# rx_1280.net
KiCad netlist of a schematic drawn in EAGLE
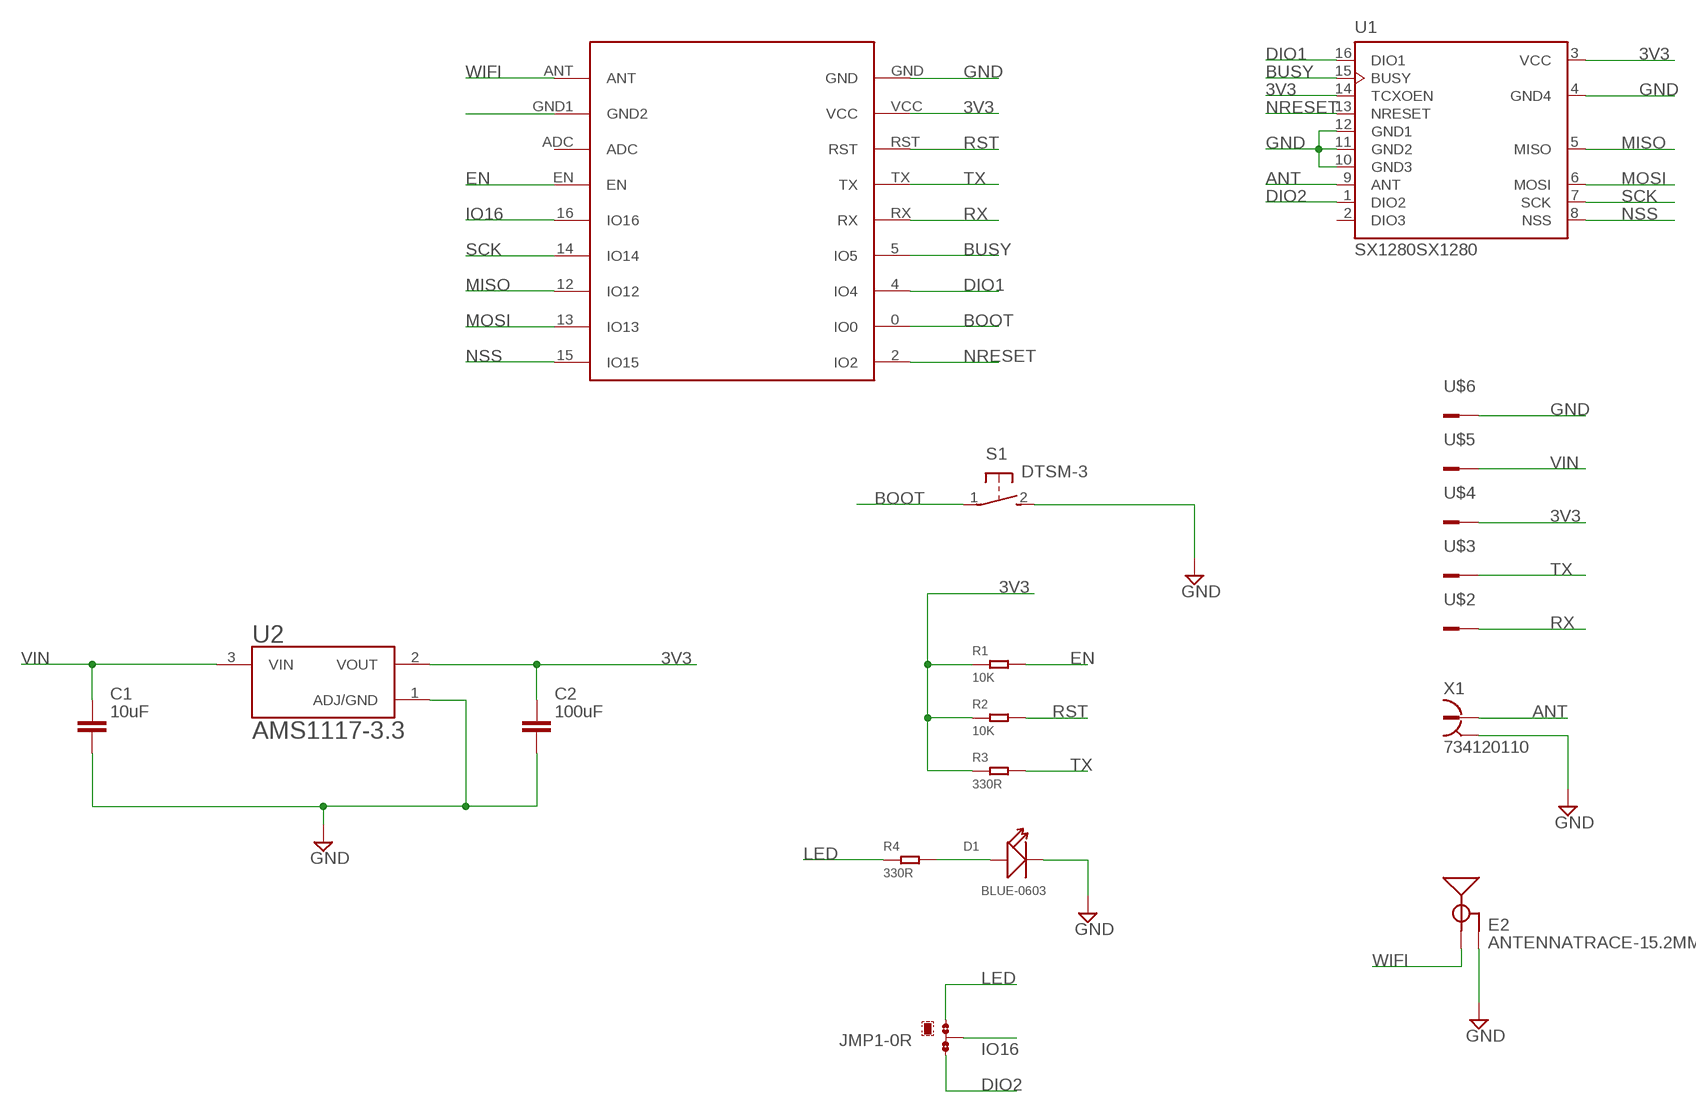
[diagram p0: schematic, sheet 1]

(export (version "E")
  (design (tool "Eeschema 10.0.6"))
  (components
    (comp (ref "C1")
      (value "10uF")
      (footprint "eagle-import:CAPM3528X210")
      (libsource (lib "eagle-import") (part "CTANTALUM-1411(3528-METRIC)_"))
    )
    (comp (ref "C2")
      (value "100uF")
      (footprint "eagle-import:CAPM3528X210")
      (libsource (lib "eagle-import") (part "CTANTALUM-1411(3528-METRIC)_"))
    )
    (comp (ref "D1")
      (value "BLUE-0603")
      (footprint "eagle-import:LED-0603")
      (fields (field (name "MPN") "19-217-BHC-ZL1M2RY-3T"))
      (libsource (lib "eagle-import") (part "SMD-LED-CLEAR-BLUE(0603)"))
    )
    (comp (ref "E2")
      (value "ANTENNATRACE-15.2MM")
      (footprint "eagle-import:TRACE_ANTENNA_2.4GHZ_15.2MM")
      (libsource (lib "eagle-import") (part "ANTENNATRACE-15.2MM"))
    )
    (comp (ref "JMP1")
      (value "0R-JUMPA")
      (footprint "eagle-import:A0R-JMP")
      (libsource (lib "eagle-import") (part "0R-JUMPA"))
    )
    (comp (ref "R1")
      (value "10K")
      (footprint "eagle-import:R0805")
      (fields (field (name "MPN") "RC0805FR-0710KL"))
      (libsource (lib "eagle-import") (part "SMD-RES-10K-1%-1/8W(0805)"))
    )
    (comp (ref "R2")
      (value "10K")
      (footprint "eagle-import:R0805")
      (fields (field (name "MPN") "RC0805FR-0710KL"))
      (libsource (lib "eagle-import") (part "SMD-RES-10K-1%-1/8W(0805)"))
    )
    (comp (ref "R3")
      (value "330R")
      (footprint "eagle-import:R0805")
      (fields (field (name "MPN") "RC0805JR-071KL"))
      (libsource (lib "eagle-import") (part "SMD-RES-330R-5%-1/8W(0805)"))
    )
    (comp (ref "R4")
      (value "330R")
      (footprint "eagle-import:R0805")
      (fields (field (name "MPN") "RC0805JR-071KL"))
      (libsource (lib "eagle-import") (part "SMD-RES-330R-5%-1/8W(0805)"))
    )
    (comp (ref "S1")
      (value "DTSM-3")
      (footprint "eagle-import:DTSM-3")
      (libsource (lib "eagle-import") (part "DTSM-3"))
    )
    (comp (ref "U$1")
      (value "ESP-M2")
      (footprint "eagle-import:ESP-M2")
      (fields
        (field (name "MF") "Doctors of Intelligence & Technology Co., LTD")
        (field (name "MP") " ESP-M2 ")
      )
      (libsource (lib "eagle-import") (part "ESP-M2"))
    )
    (comp (ref "U$2")
      (value "CONN-1")
      (footprint "eagle-import:PAD1")
      (libsource (lib "eagle-import") (part "CONN-1"))
    )
    (comp (ref "U$3")
      (value "CONN-1")
      (footprint "eagle-import:PAD1")
      (libsource (lib "eagle-import") (part "CONN-1"))
    )
    (comp (ref "U$4")
      (value "CONN-1")
      (footprint "eagle-import:PAD1")
      (libsource (lib "eagle-import") (part "CONN-1"))
    )
    (comp (ref "U$5")
      (value "CONN-1")
      (footprint "eagle-import:PAD1")
      (libsource (lib "eagle-import") (part "CONN-1"))
    )
    (comp (ref "U$6")
      (value "CONN-1")
      (footprint "eagle-import:PAD1")
      (libsource (lib "eagle-import") (part "CONN-1"))
    )
    (comp (ref "U1")
      (value "SX1280SX1280")
      (footprint "eagle-import:SX1280")
      (libsource (lib "eagle-import") (part "SX1280SX1280"))
    )
    (comp (ref "U2")
      (value "AMS1117-3.3")
      (footprint "eagle-import:SOT229P700X180-4N")
      (fields (field (name "MF") "Advanced Monolithic Systems"))
      (libsource (lib "eagle-import") (part "AMS1117-3.3"))
    )
    (comp (ref "X1")
      (value "734120110")
      (footprint "eagle-import:734120110")
      (fields (field (name "MF") "Molex") (field (name "MP") "734-12-0110"))
      (libsource (lib "eagle-import") (part "734120110"))
    )
  )
  (nets
    (net (code "1") (name "/3V3") (class "Default")
      (node (ref "C2") (pin "1") (pinfunction "1_1") (pintype "passive"))
      (node (ref "R1") (pin "1") (pinfunction "1_1") (pintype "passive"))
      (node (ref "R2") (pin "1") (pinfunction "1_1") (pintype "passive"))
      (node (ref "R3") (pin "1") (pinfunction "1_1") (pintype "passive"))
      (node (ref "U$1") (pin "VCC") (pinfunction "VCC_VCC") (pintype "bidirectional"))
      (node (ref "U$4") (pin "P$1") (pinfunction "1_P$1") (pintype "passive"))
      (node (ref "U1") (pin "14") (pinfunction "TCXOEN_14") (pintype "input"))
      (node (ref "U1") (pin "3") (pinfunction "VCC_3") (pintype "power_in"))
      (node (ref "U2") (pin "2") (pinfunction "VOUT_2") (pintype "output"))
    )
    (net (code "2") (name "/ANT") (class "Default")
      (node (ref "U1") (pin "9") (pinfunction "ANT_9") (pintype "bidirectional"))
      (node (ref "X1") (pin "1") (pinfunction "1_1") (pintype "passive"))
    )
    (net (code "3") (name "/BOOT") (class "Default")
      (node (ref "S1") (pin "1") (pinfunction "1_1") (pintype "passive"))
      (node (ref "U$1") (pin "0") (pinfunction "IO0_0") (pintype "bidirectional"))
    )
    (net (code "4") (name "/BUSY") (class "Default")
      (node (ref "U$1") (pin "5") (pinfunction "IO5_5") (pintype "bidirectional"))
      (node (ref "U1") (pin "15") (pinfunction "BUSY_15") (pintype "input"))
    )
    (net (code "5") (name "/DIO1") (class "Default")
      (node (ref "U$1") (pin "4") (pinfunction "IO4_4") (pintype "bidirectional"))
      (node (ref "U1") (pin "16") (pinfunction "DIO1_16") (pintype "input"))
    )
    (net (code "6") (name "/DIO2") (class "Default")
      (node (ref "JMP1") (pin "3") (pinfunction "3_3") (pintype "passive"))
      (node (ref "U1") (pin "1") (pinfunction "DIO2_1") (pintype "bidirectional"))
    )
    (net (code "7") (name "/EN") (class "Default")
      (node (ref "R1") (pin "2") (pinfunction "2_2") (pintype "passive"))
      (node (ref "U$1") (pin "EN") (pinfunction "EN_EN") (pintype "bidirectional"))
    )
    (net (code "8") (name "/IO16") (class "Default")
      (node (ref "JMP1") (pin "2") (pinfunction "2_2") (pintype "passive"))
      (node (ref "U$1") (pin "16") (pinfunction "IO16_16") (pintype "bidirectional"))
    )
    (net (code "9") (name "/LED") (class "Default")
      (node (ref "JMP1") (pin "1") (pinfunction "1_1") (pintype "passive"))
      (node (ref "R4") (pin "1") (pinfunction "1_1") (pintype "passive"))
    )
    (net (code "10") (name "/MISO") (class "Default")
      (node (ref "U$1") (pin "12") (pinfunction "IO12_12") (pintype "bidirectional"))
      (node (ref "U1") (pin "5") (pinfunction "MISO_5") (pintype "bidirectional"))
    )
    (net (code "11") (name "/MOSI") (class "Default")
      (node (ref "U$1") (pin "13") (pinfunction "IO13_13") (pintype "bidirectional"))
      (node (ref "U1") (pin "6") (pinfunction "MOSI_6") (pintype "bidirectional"))
    )
    (net (code "12") (name "/NRESET") (class "Default")
      (node (ref "U$1") (pin "2") (pinfunction "IO2_2") (pintype "bidirectional"))
      (node (ref "U1") (pin "13") (pinfunction "NRESET_13") (pintype "bidirectional"))
    )
    (net (code "13") (name "/NSS") (class "Default")
      (node (ref "U$1") (pin "15") (pinfunction "IO15_15") (pintype "bidirectional"))
      (node (ref "U1") (pin "8") (pinfunction "NSS_8") (pintype "bidirectional"))
    )
    (net (code "14") (name "/RST") (class "Default")
      (node (ref "R2") (pin "2") (pinfunction "2_2") (pintype "passive"))
      (node (ref "U$1") (pin "RST") (pinfunction "RST_RST") (pintype "bidirectional"))
    )
    (net (code "15") (name "/RX") (class "Default")
      (node (ref "U$1") (pin "RX") (pinfunction "RX_RX") (pintype "bidirectional"))
      (node (ref "U$2") (pin "P$1") (pinfunction "1_P$1") (pintype "passive"))
    )
    (net (code "16") (name "/SCK") (class "Default")
      (node (ref "U$1") (pin "14") (pinfunction "IO14_14") (pintype "bidirectional"))
      (node (ref "U1") (pin "7") (pinfunction "SCK_7") (pintype "bidirectional"))
    )
    (net (code "17") (name "/TX") (class "Default")
      (node (ref "R3") (pin "2") (pinfunction "2_2") (pintype "passive"))
      (node (ref "U$1") (pin "TX") (pinfunction "TX_TX") (pintype "bidirectional"))
      (node (ref "U$3") (pin "P$1") (pinfunction "1_P$1") (pintype "passive"))
    )
    (net (code "18") (name "/VIN") (class "Default")
      (node (ref "C1") (pin "1") (pinfunction "1_1") (pintype "passive"))
      (node (ref "U$5") (pin "P$1") (pinfunction "1_P$1") (pintype "passive"))
      (node (ref "U2") (pin "3") (pinfunction "VIN_3") (pintype "input"))
    )
    (net (code "19") (name "/WIFI") (class "Default")
      (node (ref "E2") (pin "ANT") (pinfunction "SIGNAL_ANT") (pintype "bidirectional"))
      (node (ref "U$1") (pin "ANT") (pinfunction "ANT_ANT") (pintype "bidirectional"))
    )
    (net (code "20") (name "GND") (class "Default")
      (node (ref "C1") (pin "2") (pinfunction "2_2") (pintype "passive"))
      (node (ref "C2") (pin "2") (pinfunction "2_2") (pintype "passive"))
      (node (ref "D1") (pin "-") (pinfunction "-_-") (pintype "passive"))
      (node (ref "E2") (pin "GND") (pinfunction "GND_GND") (pintype "bidirectional"))
      (node (ref "S1") (pin "2") (pinfunction "2_2") (pintype "passive"))
      (node (ref "U$1") (pin "GND") (pinfunction "GND_GND") (pintype "bidirectional"))
      (node (ref "U$1") (pin "GND1") (pinfunction "GND2_GND1") (pintype "bidirectional"))
      (node (ref "U$6") (pin "P$1") (pinfunction "1_P$1") (pintype "passive"))
      (node (ref "U1") (pin "10") (pinfunction "GND3_10") (pintype "power_in"))
      (node (ref "U1") (pin "11") (pinfunction "GND2_11") (pintype "power_in"))
      (node (ref "U1") (pin "12") (pinfunction "GND1_12") (pintype "power_in"))
      (node (ref "U1") (pin "4") (pinfunction "GND4_4") (pintype "power_in"))
      (node (ref "U2") (pin "1") (pinfunction "ADJ/GND_1") (pintype "power_in"))
      (node (ref "X1") (pin "S@1") (pinfunction "2_S@1") (pintype "passive"))
      (node (ref "X1") (pin "S@2") (pinfunction "2_S@2") (pintype "passive"))
      (node (ref "X1") (pin "S@3") (pinfunction "2_S@3") (pintype "passive"))
    )
    (net (code "21") (name "Net-(D1-Pad+)") (class "Default")
      (node (ref "D1") (pin "+") (pinfunction "+_+") (pintype "passive"))
      (node (ref "R4") (pin "2") (pinfunction "2_2") (pintype "passive"))
    )
    (net (code "22") (name "unconnected-(U$1-PadADC)") (class "Default")
      (node (ref "U$1") (pin "ADC") (pinfunction "ADC_ADC") (pintype "bidirectional"))
    )
    (net (code "23") (name "unconnected-(U1-DIO3-Pad2)") (class "Default")
      (node (ref "U1") (pin "2") (pinfunction "DIO3_2") (pintype "bidirectional"))
    )
  )
)
